# FI2_BF998.net
KiCad netlist of a schematic drawn in Altium Designer
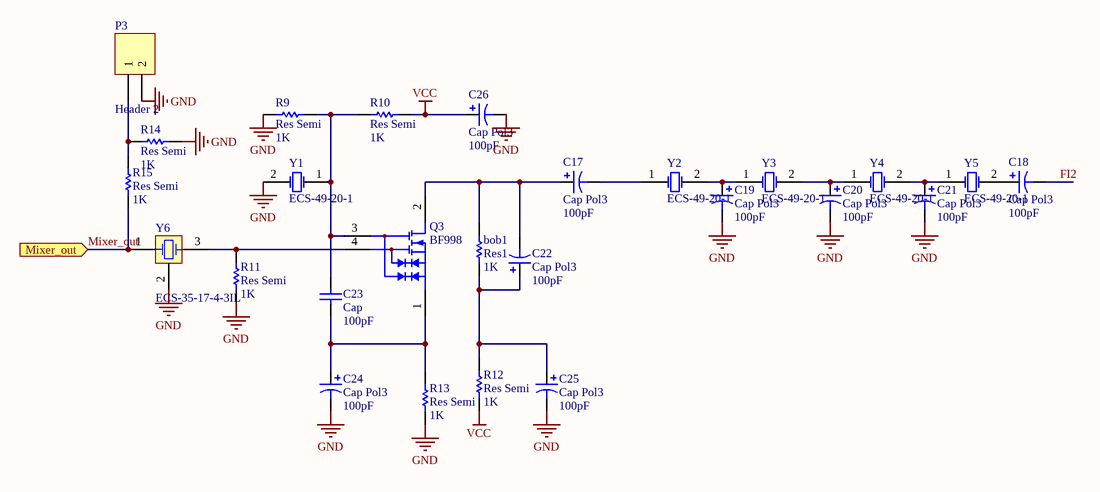
[diagram p0: FI2_BF998.SchDoc]

(export (version "E")
  (design (tool "Eeschema 10.0.6"))
  (components
    (comp (ref "bob1")
      (value "Res1")
      (footprint "AXIAL-0.3")
      (description "Resistor")
      (fields (field (name "ALTIUM_VALUE") "1K") (field (name "PUBLISHER") "Altium Limited"))
      (libsource (lib "Miscellaneous Devices") (part "Res1"))
    )
    (comp (ref "C17")
      (value "Cap Pol3")
      (footprint "C0805")
      (description "Polarized Capacitor (Surface Mount)")
      (fields (field (name "ALTIUM_VALUE") "100pF") (field (name "PUBLISHER") "Altium Limited"))
      (libsource (lib "Miscellaneous Devices") (part "Cap Pol3"))
    )
    (comp (ref "C18")
      (value "Cap Pol3")
      (footprint "C0805")
      (description "Polarized Capacitor (Surface Mount)")
      (fields (field (name "ALTIUM_VALUE") "100pF") (field (name "PUBLISHER") "Altium Limited"))
      (libsource (lib "Miscellaneous Devices") (part "Cap Pol3"))
    )
    (comp (ref "C19")
      (value "Cap Pol3")
      (footprint "C0805")
      (description "Polarized Capacitor (Surface Mount)")
      (fields (field (name "ALTIUM_VALUE") "100pF") (field (name "PUBLISHER") "Altium Limited"))
      (libsource (lib "Miscellaneous Devices") (part "Cap Pol3"))
    )
    (comp (ref "C20")
      (value "Cap Pol3")
      (footprint "C0805")
      (description "Polarized Capacitor (Surface Mount)")
      (fields (field (name "ALTIUM_VALUE") "100pF") (field (name "PUBLISHER") "Altium Limited"))
      (libsource (lib "Miscellaneous Devices") (part "Cap Pol3"))
    )
    (comp (ref "C21")
      (value "Cap Pol3")
      (footprint "C0805")
      (description "Polarized Capacitor (Surface Mount)")
      (fields (field (name "ALTIUM_VALUE") "100pF") (field (name "PUBLISHER") "Altium Limited"))
      (libsource (lib "Miscellaneous Devices") (part "Cap Pol3"))
    )
    (comp (ref "C22")
      (value "Cap Pol3")
      (footprint "C0805")
      (description "Polarized Capacitor (Surface Mount)")
      (fields (field (name "ALTIUM_VALUE") "100pF") (field (name "PUBLISHER") "Altium Limited"))
      (libsource (lib "Miscellaneous Devices") (part "Cap Pol3"))
    )
    (comp (ref "C23")
      (value "Cap")
      (footprint "VP45-3.2")
      (description "Capacitor")
      (fields (field (name "ALTIUM_VALUE") "100pF") (field (name "PUBLISHER") "Altium Limited"))
      (libsource (lib "Miscellaneous Devices") (part "Cap"))
    )
    (comp (ref "C24")
      (value "Cap Pol3")
      (footprint "C0805")
      (description "Polarized Capacitor (Surface Mount)")
      (fields (field (name "ALTIUM_VALUE") "100pF") (field (name "PUBLISHER") "Altium Limited"))
      (libsource (lib "Miscellaneous Devices") (part "Cap Pol3"))
    )
    (comp (ref "C25")
      (value "Cap Pol3")
      (footprint "C0805")
      (description "Polarized Capacitor (Surface Mount)")
      (fields (field (name "ALTIUM_VALUE") "100pF") (field (name "PUBLISHER") "Altium Limited"))
      (libsource (lib "Miscellaneous Devices") (part "Cap Pol3"))
    )
    (comp (ref "C26")
      (value "Cap Pol3")
      (footprint "C0805")
      (description "Polarized Capacitor (Surface Mount)")
      (fields (field (name "ALTIUM_VALUE") "100pF") (field (name "PUBLISHER") "Altium Limited"))
      (libsource (lib "Miscellaneous Devices") (part "Cap Pol3"))
    )
    (comp (ref "P3")
      (value "Header 2")
      (footprint "HDR1X2")
      (description "Header, 2-Pin")
      (fields (field (name "PUBLISHER") "Altium Limited"))
      (libsource (lib "Miscellaneous Connectors") (part "Header 2"))
    )
    (comp (ref "Q3")
      (value "BF998")
      (footprint "SOT143_N")
      (description "Silicon N-channel Dual-gate MOSFET")
      (fields (field (name "PUBLISHER") "Altium Limited"))
      (libsource (lib "Philips Discrete MOSFET - Low Power") (part "BF998"))
    )
    (comp (ref "R9")
      (value "Res Semi")
      (footprint "2012[0805]")
      (description "Semiconductor Resistor")
      (fields (field (name "ALTIUM_VALUE") "1K") (field (name "PUBLISHER") "Altium Limited"))
      (libsource (lib "Miscellaneous Devices") (part "Res Semi"))
    )
    (comp (ref "R10")
      (value "Res Semi")
      (footprint "2012[0805]")
      (description "Semiconductor Resistor")
      (fields (field (name "ALTIUM_VALUE") "1K") (field (name "PUBLISHER") "Altium Limited"))
      (libsource (lib "Miscellaneous Devices") (part "Res Semi"))
    )
    (comp (ref "R11")
      (value "Res Semi")
      (footprint "2012[0805]")
      (description "Semiconductor Resistor")
      (fields (field (name "ALTIUM_VALUE") "1K") (field (name "PUBLISHER") "Altium Limited"))
      (libsource (lib "Miscellaneous Devices") (part "Res Semi"))
    )
    (comp (ref "R12")
      (value "Res Semi")
      (footprint "2012[0805]")
      (description "Semiconductor Resistor")
      (fields (field (name "ALTIUM_VALUE") "1K") (field (name "PUBLISHER") "Altium Limited"))
      (libsource (lib "Miscellaneous Devices") (part "Res Semi"))
    )
    (comp (ref "R13")
      (value "Res Semi")
      (footprint "2012[0805]")
      (description "Semiconductor Resistor")
      (fields (field (name "ALTIUM_VALUE") "1K") (field (name "PUBLISHER") "Altium Limited"))
      (libsource (lib "Miscellaneous Devices") (part "Res Semi"))
    )
    (comp (ref "R14")
      (value "Res Semi")
      (footprint "2012[0805]")
      (description "Semiconductor Resistor")
      (fields (field (name "ALTIUM_VALUE") "1K") (field (name "PUBLISHER") "Altium Limited"))
      (libsource (lib "Miscellaneous Devices") (part "Res Semi"))
    )
    (comp (ref "R15")
      (value "Res Semi")
      (footprint "2012[0805]")
      (description "Semiconductor Resistor")
      (fields (field (name "ALTIUM_VALUE") "1K") (field (name "PUBLISHER") "Altium Limited"))
      (libsource (lib "Miscellaneous Devices") (part "Res Semi"))
    )
    (comp (ref "Y1")
      (value "ECS-49-20-1")
      (footprint "HC-49U")
      (description "Crystal Oscillator")
      (fields (field (name "PUBLISHER") "Altium Limited"))
      (libsource (lib "ECS Crystal Oscillator") (part "ECS-49-20-1"))
    )
    (comp (ref "Y2")
      (value "ECS-49-20-1")
      (footprint "HC-49U")
      (description "Crystal Oscillator")
      (fields (field (name "PUBLISHER") "Altium Limited"))
      (libsource (lib "ECS Crystal Oscillator") (part "ECS-49-20-1"))
    )
    (comp (ref "Y3")
      (value "ECS-49-20-1")
      (footprint "HC-49U")
      (description "Crystal Oscillator")
      (fields (field (name "PUBLISHER") "Altium Limited"))
      (libsource (lib "ECS Crystal Oscillator") (part "ECS-49-20-1"))
    )
    (comp (ref "Y4")
      (value "ECS-49-20-1")
      (footprint "HC-49U")
      (description "Crystal Oscillator")
      (fields (field (name "PUBLISHER") "Altium Limited"))
      (libsource (lib "ECS Crystal Oscillator") (part "ECS-49-20-1"))
    )
    (comp (ref "Y5")
      (value "ECS-49-20-1")
      (footprint "HC-49U")
      (description "Crystal Oscillator")
      (fields (field (name "PUBLISHER") "Altium Limited"))
      (libsource (lib "ECS Crystal Oscillator") (part "ECS-49-20-1"))
    )
    (comp (ref "Y6")
      (value "ECS-35-17-4-3IL")
      (footprint "HC-49US")
      (description "Crystal Oscillator, 3rd In-Line Lead Version")
      (fields (field (name "PUBLISHER") "Altium Limited"))
      (libsource (lib "ECS Crystal Oscillator") (part "ECS-35-17-4-3IL"))
    )
  )
  (nets
    (net (code "1") (name "/FI2") (class "Default")
      (node (ref "C18") (pin "2") (pinfunction "2_2") (pintype "passive"))
    )
    (net (code "2") (name "/Mixer_out") (class "Default")
      (node (ref "R15") (pin "1") (pinfunction "1_1") (pintype "passive"))
      (node (ref "Y6") (pin "1") (pinfunction "OSC1_1") (pintype "passive"))
    )
    (net (code "3") (name "GND") (class "Default")
      (node (ref "C19") (pin "2") (pinfunction "2_2") (pintype "passive"))
      (node (ref "C20") (pin "2") (pinfunction "2_2") (pintype "passive"))
      (node (ref "C21") (pin "2") (pinfunction "2_2") (pintype "passive"))
      (node (ref "C24") (pin "2") (pinfunction "2_2") (pintype "passive"))
      (node (ref "C25") (pin "2") (pinfunction "2_2") (pintype "passive"))
      (node (ref "C26") (pin "2") (pinfunction "2_2") (pintype "passive"))
      (node (ref "P3") (pin "2") (pinfunction "2_2") (pintype "passive"))
      (node (ref "R11") (pin "1") (pinfunction "1_1") (pintype "passive"))
      (node (ref "R13") (pin "1") (pinfunction "1_1") (pintype "passive"))
      (node (ref "R14") (pin "1") (pinfunction "1_1") (pintype "passive"))
      (node (ref "R9") (pin "2") (pinfunction "2_2") (pintype "passive"))
      (node (ref "Y1") (pin "2") (pinfunction "OSC2_2") (pintype "passive"))
      (node (ref "Y6") (pin "2") (pinfunction "COM_2") (pintype "passive"))
    )
    (net (code "4") (name "Net-(C22-Pad1)") (class "Default")
      (node (ref "C22") (pin "1") (pinfunction "1_1") (pintype "passive"))
      (node (ref "C25") (pin "1") (pinfunction "1_1") (pintype "passive"))
      (node (ref "R12") (pin "2") (pinfunction "2_2") (pintype "passive"))
      (node (ref "bob1") (pin "1") (pinfunction "1_1") (pintype "passive"))
    )
    (net (code "5") (name "Net-(P3-Pad1)") (class "Default")
      (node (ref "P3") (pin "1") (pinfunction "1_1") (pintype "passive"))
      (node (ref "R14") (pin "2") (pinfunction "2_2") (pintype "passive"))
      (node (ref "R15") (pin "2") (pinfunction "2_2") (pintype "passive"))
    )
    (net (code "6") (name "Net-(Q3-D)") (class "Default")
      (node (ref "C17") (pin "1") (pinfunction "1_1") (pintype "passive"))
      (node (ref "C22") (pin "2") (pinfunction "2_2") (pintype "passive"))
      (node (ref "Q3") (pin "2") (pinfunction "D_2") (pintype "passive"))
      (node (ref "bob1") (pin "2") (pinfunction "2_2") (pintype "passive"))
    )
    (net (code "7") (name "Net-(Q3-G1)") (class "Default")
      (node (ref "Q3") (pin "4") (pinfunction "G1_4") (pintype "passive"))
      (node (ref "R11") (pin "2") (pinfunction "2_2") (pintype "passive"))
      (node (ref "Y6") (pin "3") (pinfunction "OSC2_3") (pintype "passive"))
    )
    (net (code "8") (name "Net-(Q3-G2)") (class "Default")
      (node (ref "C23") (pin "2") (pinfunction "2_2") (pintype "passive"))
      (node (ref "Q3") (pin "3") (pinfunction "G2_3") (pintype "passive"))
      (node (ref "R10") (pin "2") (pinfunction "2_2") (pintype "passive"))
      (node (ref "R9") (pin "1") (pinfunction "1_1") (pintype "passive"))
      (node (ref "Y1") (pin "1") (pinfunction "OSC1_1") (pintype "passive"))
    )
    (net (code "9") (name "Net-(Q3-S)") (class "Default")
      (node (ref "C23") (pin "1") (pinfunction "1_1") (pintype "passive"))
      (node (ref "C24") (pin "1") (pinfunction "1_1") (pintype "passive"))
      (node (ref "Q3") (pin "1") (pinfunction "S_1") (pintype "passive"))
      (node (ref "R13") (pin "2") (pinfunction "2_2") (pintype "passive"))
    )
    (net (code "10") (name "Net-(Y2-OSC1)") (class "Default")
      (node (ref "C17") (pin "2") (pinfunction "2_2") (pintype "passive"))
      (node (ref "Y2") (pin "1") (pinfunction "OSC1_1") (pintype "passive"))
    )
    (net (code "11") (name "Net-(Y2-OSC2)") (class "Default")
      (node (ref "C19") (pin "1") (pinfunction "1_1") (pintype "passive"))
      (node (ref "Y2") (pin "2") (pinfunction "OSC2_2") (pintype "passive"))
      (node (ref "Y3") (pin "1") (pinfunction "OSC1_1") (pintype "passive"))
    )
    (net (code "12") (name "Net-(Y3-OSC2)") (class "Default")
      (node (ref "C20") (pin "1") (pinfunction "1_1") (pintype "passive"))
      (node (ref "Y3") (pin "2") (pinfunction "OSC2_2") (pintype "passive"))
      (node (ref "Y4") (pin "1") (pinfunction "OSC1_1") (pintype "passive"))
    )
    (net (code "13") (name "Net-(Y4-OSC2)") (class "Default")
      (node (ref "C21") (pin "1") (pinfunction "1_1") (pintype "passive"))
      (node (ref "Y4") (pin "2") (pinfunction "OSC2_2") (pintype "passive"))
      (node (ref "Y5") (pin "1") (pinfunction "OSC1_1") (pintype "passive"))
    )
    (net (code "14") (name "Net-(Y5-OSC2)") (class "Default")
      (node (ref "C18") (pin "1") (pinfunction "1_1") (pintype "passive"))
      (node (ref "Y5") (pin "2") (pinfunction "OSC2_2") (pintype "passive"))
    )
    (net (code "15") (name "VCC") (class "Default")
      (node (ref "C26") (pin "1") (pinfunction "1_1") (pintype "passive"))
      (node (ref "R10") (pin "1") (pinfunction "1_1") (pintype "passive"))
      (node (ref "R12") (pin "1") (pinfunction "1_1") (pintype "passive"))
    )
  )
)
